# PCIE_x1_Edge_Connector_Interface.net
KiCad netlist of a schematic drawn in Altium Designer
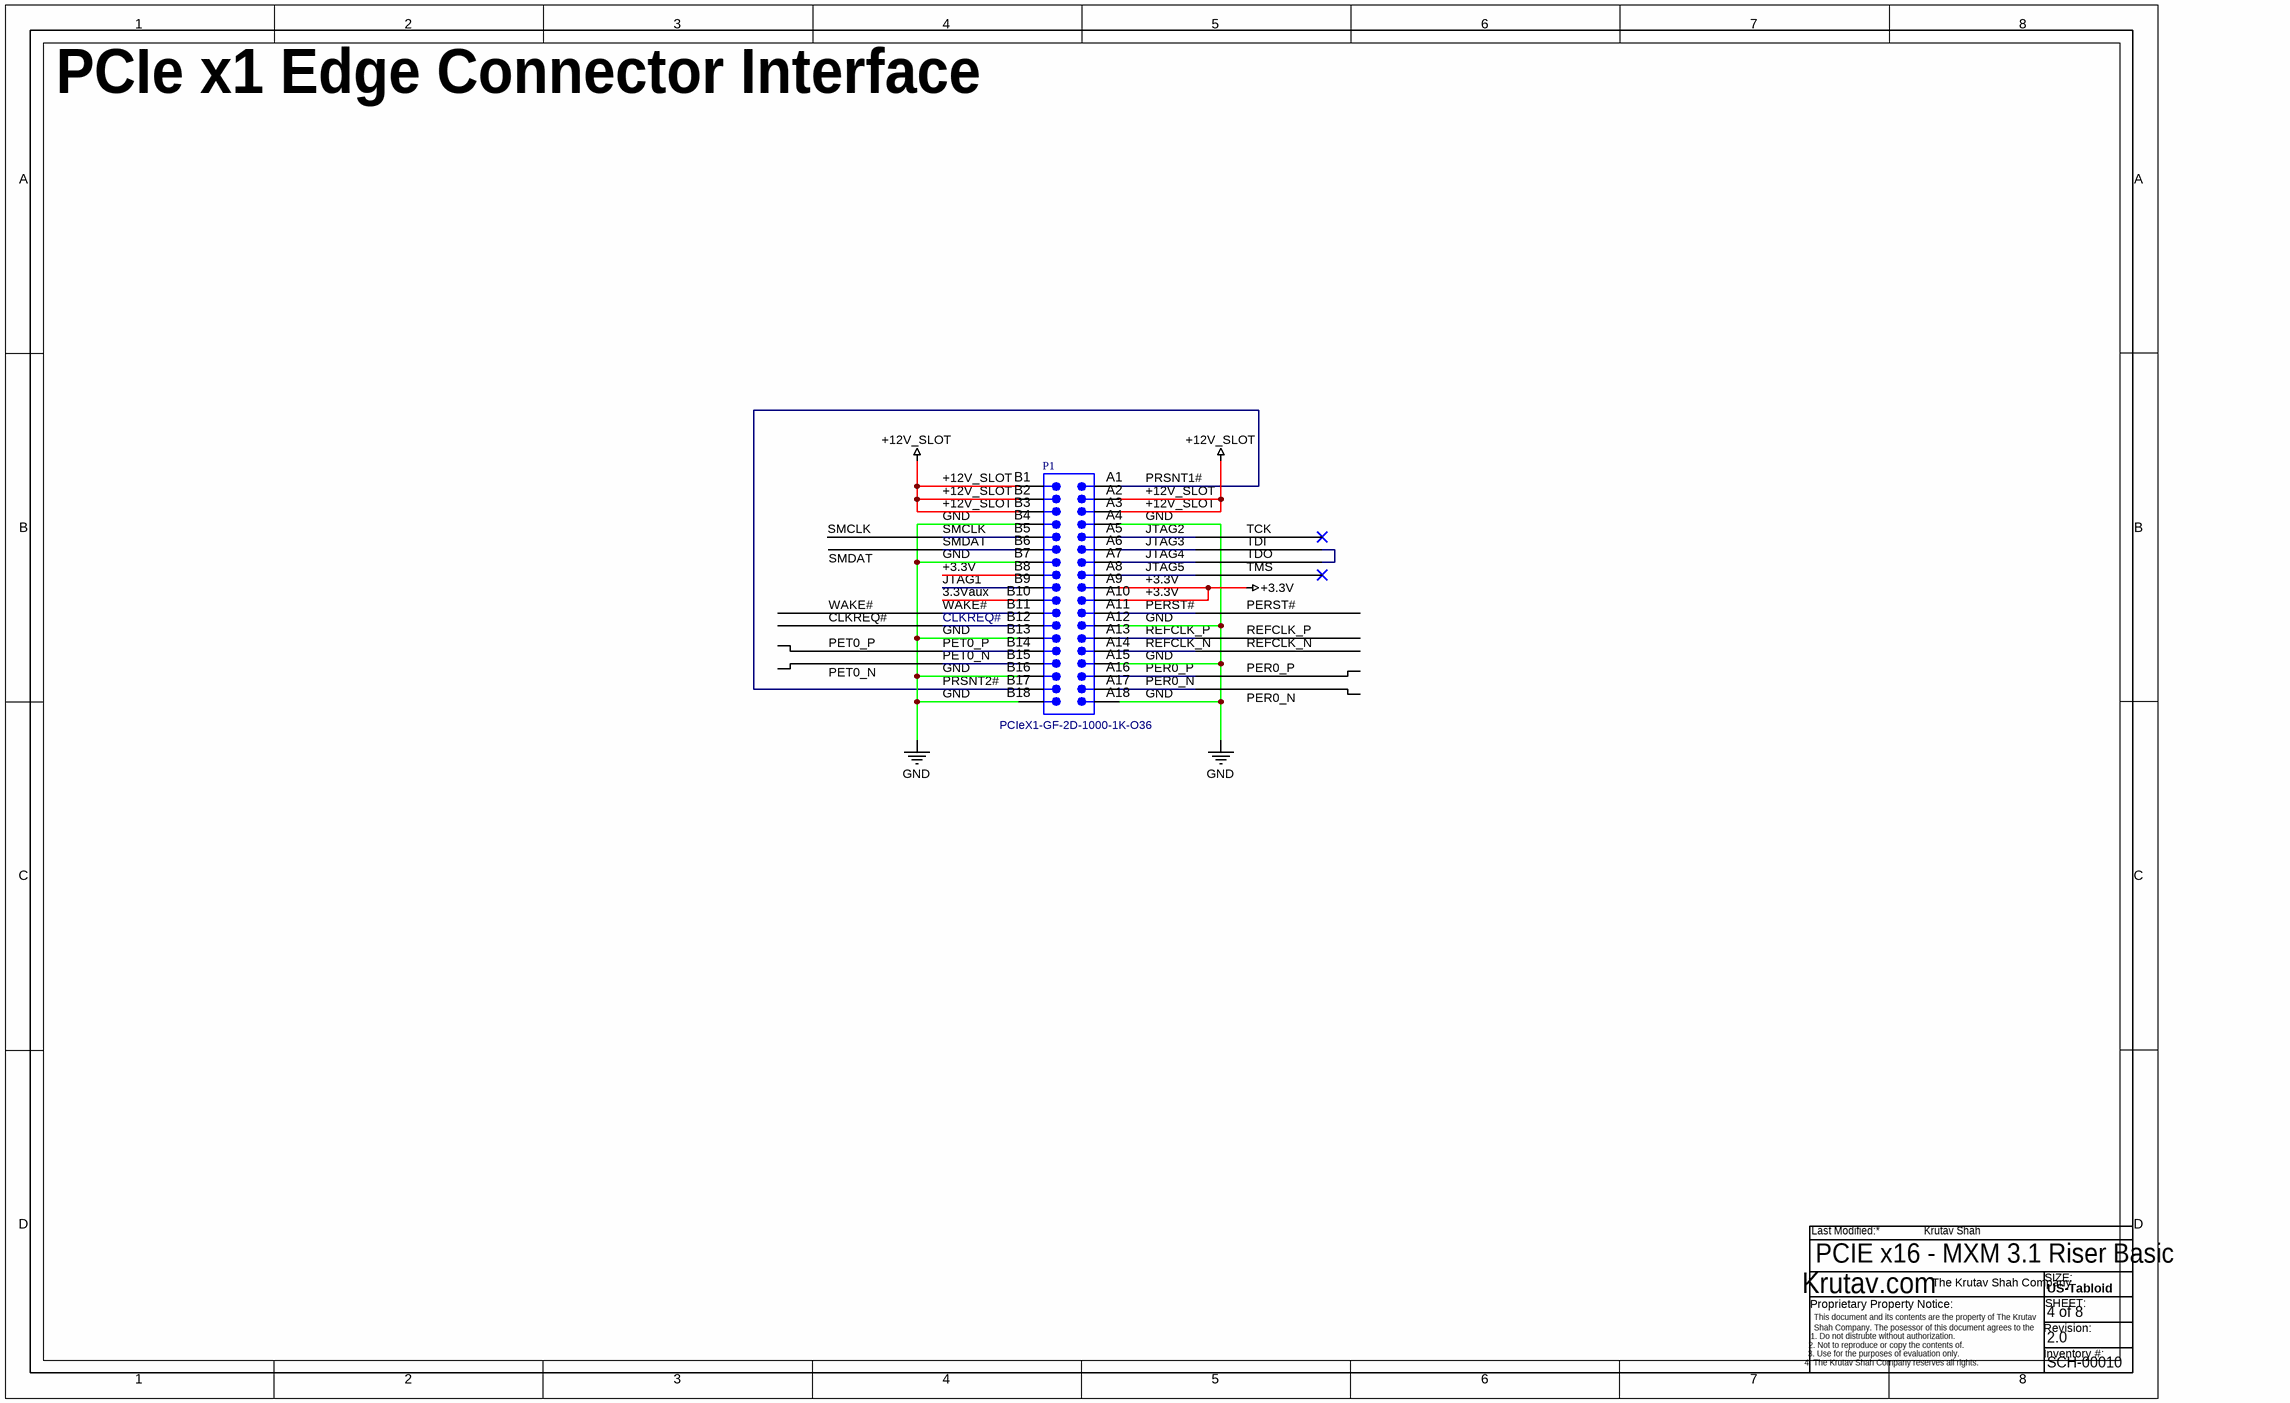
[diagram p0: PCIE x1 Edge Connector Interface.SchDoc]

(export (version "E")
  (design (tool "Eeschema 10.0.6"))
  (components
    (comp (ref "P1")
      (value "PCIeX1-GF-2D-1000-1K-O36")
      (footprint "PCIeX1-GF-2D-1000-1K-O36")
      (description "Golden finger, PCIeX1, Dual, Opposite, Pitch 1mm, 36-Position")
      (fields (field (name "PUBLISHER") "Altium"))
      (libsource (lib "Altium Shanghai") (part "PCIeX1-GF-2D-1000-1K-O36"))
    )
  )
  (nets
    (net (code "1") (name "+3.3V") (class "Default")
      (node (ref "P1") (pin "A10") (pinfunction "A10_A10") (pintype "passive"))
      (node (ref "P1") (pin "A9") (pinfunction "A9_A9") (pintype "passive"))
      (node (ref "P1") (pin "B8") (pinfunction "B8_B8") (pintype "passive"))
    )
    (net (code "2") (name "+12V_SLOT") (class "Default")
      (node (ref "P1") (pin "A2") (pinfunction "A2_A2") (pintype "passive"))
      (node (ref "P1") (pin "A3") (pinfunction "A3_A3") (pintype "passive"))
      (node (ref "P1") (pin "B1") (pinfunction "B1_B1") (pintype "passive"))
      (node (ref "P1") (pin "B2") (pinfunction "B2_B2") (pintype "passive"))
      (node (ref "P1") (pin "B3") (pinfunction "B3_B3") (pintype "passive"))
    )
    (net (code "3") (name "/3.3Vaux") (class "Default")
      (node (ref "P1") (pin "B10") (pinfunction "B10_B10") (pintype "passive"))
    )
    (net (code "4") (name "/CLKREQ#") (class "Default")
      (node (ref "P1") (pin "B12") (pinfunction "B12_B12") (pintype "passive"))
    )
    (net (code "5") (name "/JTAG1") (class "Default")
      (node (ref "P1") (pin "B9") (pinfunction "B9_B9") (pintype "passive"))
    )
    (net (code "6") (name "/JTAG2") (class "Default")
      (node (ref "P1") (pin "A5") (pinfunction "A5_A5") (pintype "passive+no_connect"))
    )
    (net (code "7") (name "/JTAG3") (class "Default")
      (node (ref "P1") (pin "A6") (pinfunction "A6_A6") (pintype "passive"))
      (node (ref "P1") (pin "A7") (pinfunction "A7_A7") (pintype "passive"))
    )
    (net (code "8") (name "/JTAG5") (class "Default")
      (node (ref "P1") (pin "A8") (pinfunction "A8_A8") (pintype "passive+no_connect"))
    )
    (net (code "9") (name "/PER0_N") (class "Default")
      (node (ref "P1") (pin "A17") (pinfunction "A17_A17") (pintype "passive"))
    )
    (net (code "10") (name "/PER0_P") (class "Default")
      (node (ref "P1") (pin "A16") (pinfunction "A16_A16") (pintype "passive"))
    )
    (net (code "11") (name "/PERST#") (class "Default")
      (node (ref "P1") (pin "A11") (pinfunction "A11_A11") (pintype "passive"))
    )
    (net (code "12") (name "/PET0_N") (class "Default")
      (node (ref "P1") (pin "B15") (pinfunction "B15_B15") (pintype "passive"))
    )
    (net (code "13") (name "/PET0_P") (class "Default")
      (node (ref "P1") (pin "B14") (pinfunction "B14_B14") (pintype "passive"))
    )
    (net (code "14") (name "/PRSNT1#") (class "Default")
      (node (ref "P1") (pin "A1") (pinfunction "A1_A1") (pintype "passive"))
      (node (ref "P1") (pin "B17") (pinfunction "B17_B17") (pintype "passive"))
    )
    (net (code "15") (name "/REFCLK_N") (class "Default")
      (node (ref "P1") (pin "A14") (pinfunction "A14_A14") (pintype "passive"))
    )
    (net (code "16") (name "/REFCLK_P") (class "Default")
      (node (ref "P1") (pin "A13") (pinfunction "A13_A13") (pintype "passive"))
    )
    (net (code "17") (name "/SMCLK") (class "Default")
      (node (ref "P1") (pin "B5") (pinfunction "B5_B5") (pintype "passive"))
    )
    (net (code "18") (name "/SMDAT") (class "Default")
      (node (ref "P1") (pin "B6") (pinfunction "B6_B6") (pintype "passive"))
    )
    (net (code "19") (name "/WAKE#") (class "Default")
      (node (ref "P1") (pin "B11") (pinfunction "B11_B11") (pintype "passive"))
    )
    (net (code "20") (name "GND") (class "Default")
      (node (ref "P1") (pin "A12") (pinfunction "A12_A12") (pintype "passive"))
      (node (ref "P1") (pin "A15") (pinfunction "A15_A15") (pintype "passive"))
      (node (ref "P1") (pin "A18") (pinfunction "A18_A18") (pintype "passive"))
      (node (ref "P1") (pin "A4") (pinfunction "A4_A4") (pintype "passive"))
      (node (ref "P1") (pin "B13") (pinfunction "B13_B13") (pintype "passive"))
      (node (ref "P1") (pin "B16") (pinfunction "B16_B16") (pintype "passive"))
      (node (ref "P1") (pin "B18") (pinfunction "B18_B18") (pintype "passive"))
      (node (ref "P1") (pin "B4") (pinfunction "B4_B4") (pintype "passive"))
      (node (ref "P1") (pin "B7") (pinfunction "B7_B7") (pintype "passive"))
    )
  )
)
